# tastatur.net
KiCad netlist of a schematic drawn in EAGLE
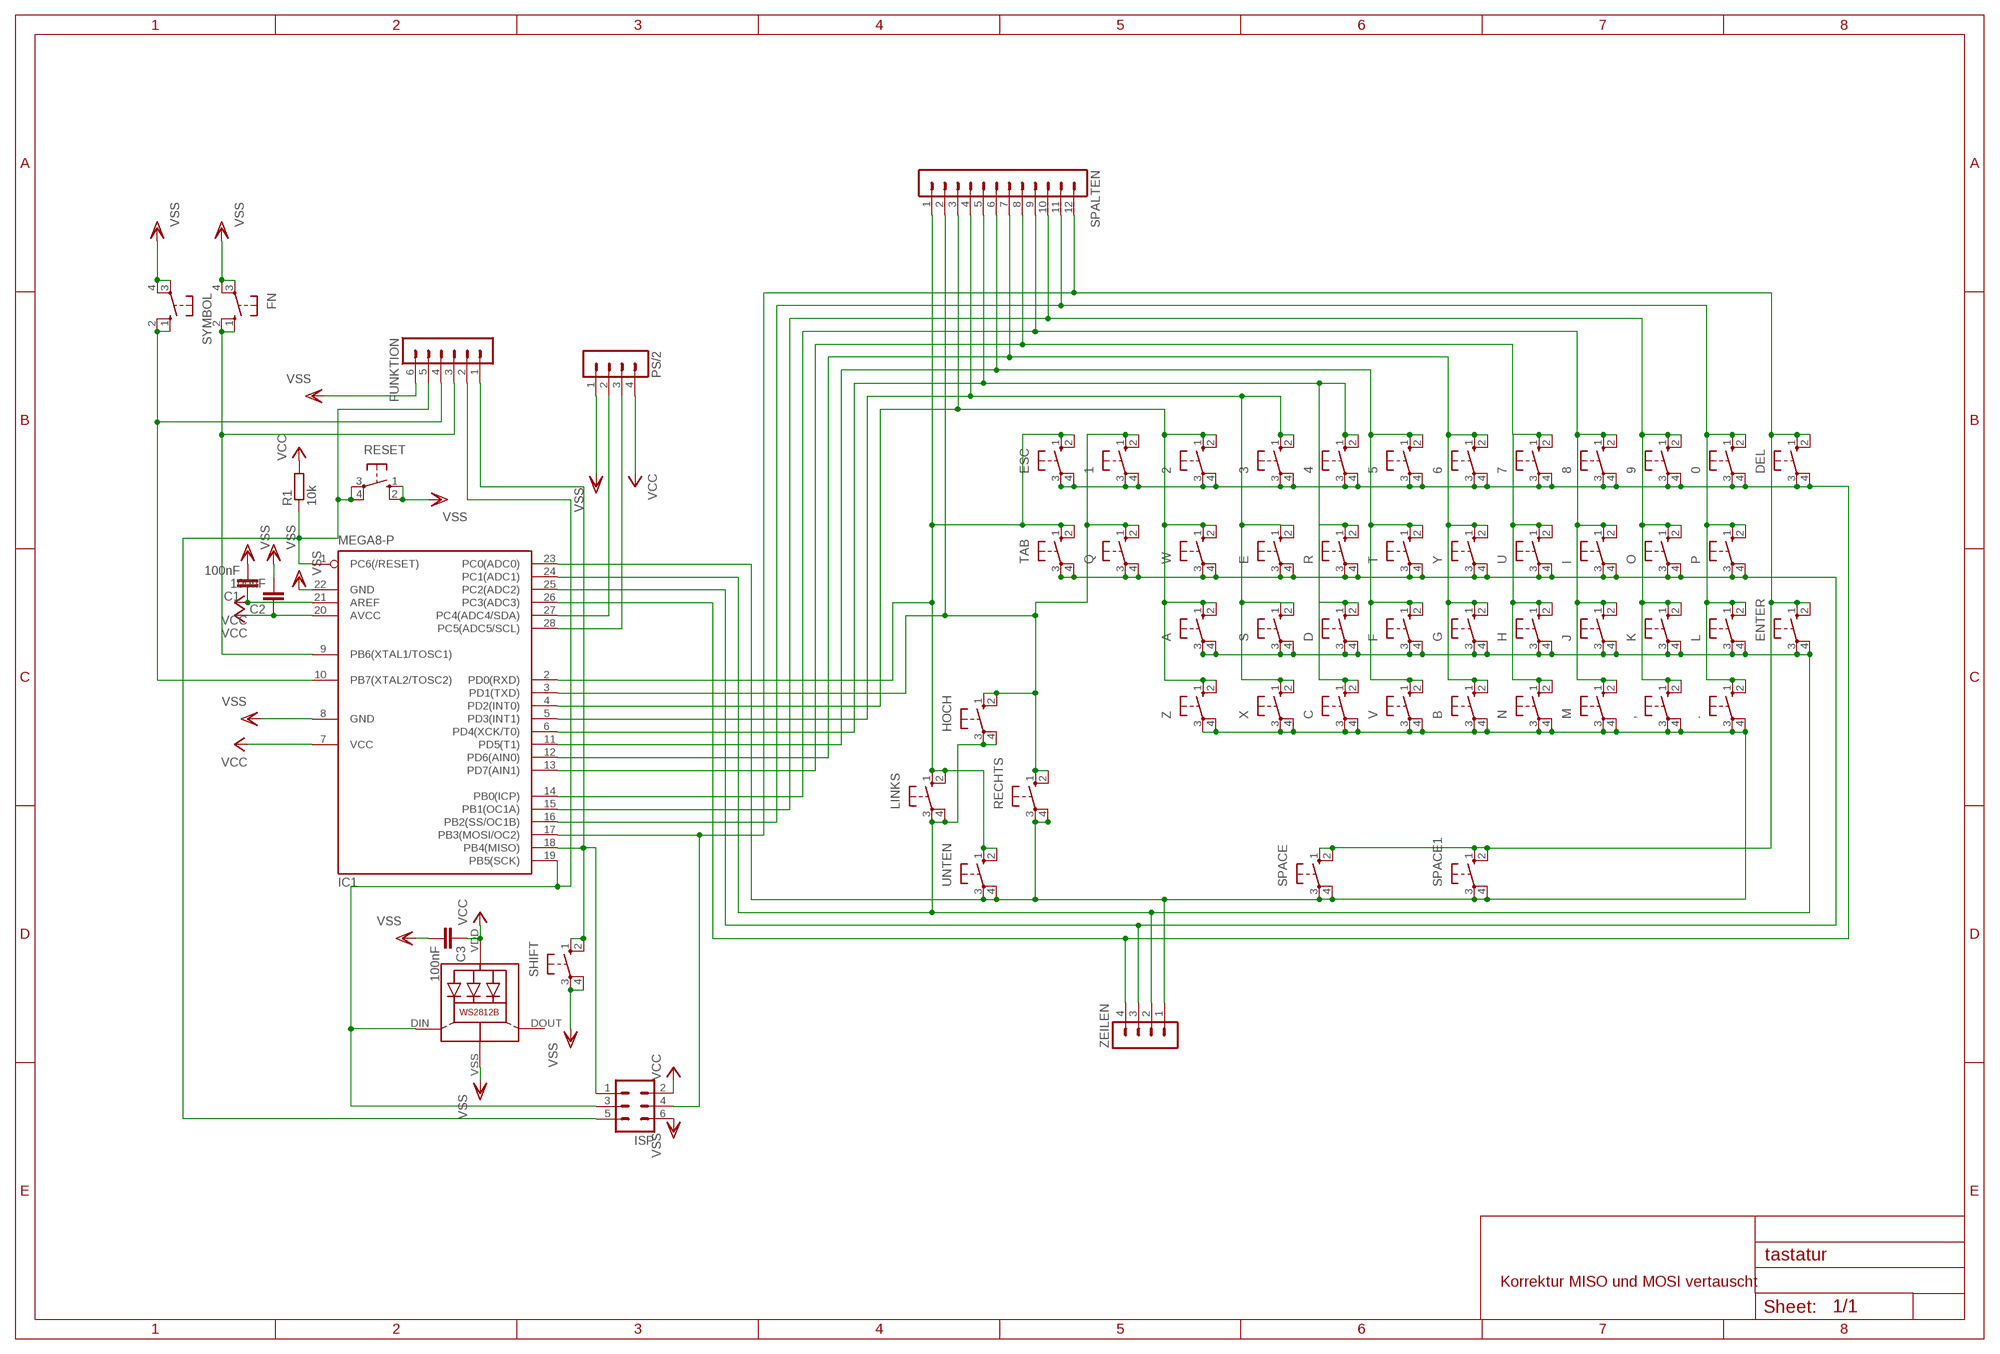
[diagram p0: schematic, sheet 1]

(export (version "E")
  (design (tool "Eeschema 10.0.6"))
  (components
    (comp (ref ",")
      (value "40-XX")
      (footprint "eagle-import:B3F-40XX")
      (fields (field (name "MF") "OMRON COMPONENTS USA") (field (name "MPN") "B3F-4000"))
      (libsource (lib "eagle-import") (part "40-XX"))
    )
    (comp (ref ".")
      (value "40-XX")
      (footprint "eagle-import:B3F-40XX")
      (fields (field (name "MF") "OMRON COMPONENTS USA") (field (name "MPN") "B3F-4000"))
      (libsource (lib "eagle-import") (part "40-XX"))
    )
    (comp (ref "0")
      (value "40-XX")
      (footprint "eagle-import:B3F-40XX")
      (fields (field (name "MF") "OMRON COMPONENTS USA") (field (name "MPN") "B3F-4000"))
      (libsource (lib "eagle-import") (part "40-XX"))
    )
    (comp (ref "1")
      (value "40-XX")
      (footprint "eagle-import:B3F-40XX")
      (fields (field (name "MF") "OMRON COMPONENTS USA") (field (name "MPN") "B3F-4000"))
      (libsource (lib "eagle-import") (part "40-XX"))
    )
    (comp (ref "2")
      (value "40-XX")
      (footprint "eagle-import:B3F-40XX")
      (fields (field (name "MF") "OMRON COMPONENTS USA") (field (name "MPN") "B3F-4000"))
      (libsource (lib "eagle-import") (part "40-XX"))
    )
    (comp (ref "3")
      (value "40-XX")
      (footprint "eagle-import:B3F-40XX")
      (fields (field (name "MF") "OMRON COMPONENTS USA") (field (name "MPN") "B3F-4000"))
      (libsource (lib "eagle-import") (part "40-XX"))
    )
    (comp (ref "4")
      (value "40-XX")
      (footprint "eagle-import:B3F-40XX")
      (fields (field (name "MF") "OMRON COMPONENTS USA") (field (name "MPN") "B3F-4000"))
      (libsource (lib "eagle-import") (part "40-XX"))
    )
    (comp (ref "5")
      (value "40-XX")
      (footprint "eagle-import:B3F-40XX")
      (fields (field (name "MF") "OMRON COMPONENTS USA") (field (name "MPN") "B3F-4000"))
      (libsource (lib "eagle-import") (part "40-XX"))
    )
    (comp (ref "6")
      (value "40-XX")
      (footprint "eagle-import:B3F-40XX")
      (fields (field (name "MF") "OMRON COMPONENTS USA") (field (name "MPN") "B3F-4000"))
      (libsource (lib "eagle-import") (part "40-XX"))
    )
    (comp (ref "7")
      (value "40-XX")
      (footprint "eagle-import:B3F-40XX")
      (fields (field (name "MF") "OMRON COMPONENTS USA") (field (name "MPN") "B3F-4000"))
      (libsource (lib "eagle-import") (part "40-XX"))
    )
    (comp (ref "8")
      (value "40-XX")
      (footprint "eagle-import:B3F-40XX")
      (fields (field (name "MF") "OMRON COMPONENTS USA") (field (name "MPN") "B3F-4000"))
      (libsource (lib "eagle-import") (part "40-XX"))
    )
    (comp (ref "9")
      (value "40-XX")
      (footprint "eagle-import:B3F-40XX")
      (fields (field (name "MF") "OMRON COMPONENTS USA") (field (name "MPN") "B3F-4000"))
      (libsource (lib "eagle-import") (part "40-XX"))
    )
    (comp (ref "A")
      (value "40-XX")
      (footprint "eagle-import:B3F-40XX")
      (fields (field (name "MF") "OMRON COMPONENTS USA") (field (name "MPN") "B3F-4000"))
      (libsource (lib "eagle-import") (part "40-XX"))
    )
    (comp (ref "B")
      (value "40-XX")
      (footprint "eagle-import:B3F-40XX")
      (fields (field (name "MF") "OMRON COMPONENTS USA") (field (name "MPN") "B3F-4000"))
      (libsource (lib "eagle-import") (part "40-XX"))
    )
    (comp (ref "C")
      (value "40-XX")
      (footprint "eagle-import:B3F-40XX")
      (fields (field (name "MF") "OMRON COMPONENTS USA") (field (name "MPN") "B3F-4000"))
      (libsource (lib "eagle-import") (part "40-XX"))
    )
    (comp (ref "C1")
      (value "100nF")
      (footprint "eagle-import:C025-025X050")
      (libsource (lib "eagle-import") (part "C-EU025-025X050"))
    )
    (comp (ref "C2")
      (value "100nF")
      (footprint "eagle-import:C025-025X050")
      (libsource (lib "eagle-import") (part "C-EU025-025X050"))
    )
    (comp (ref "C3")
      (value "100nF")
      (footprint "eagle-import:C025-025X050")
      (libsource (lib "eagle-import") (part "C-EU025-025X050"))
    )
    (comp (ref "D")
      (value "40-XX")
      (footprint "eagle-import:B3F-40XX")
      (fields (field (name "MF") "OMRON COMPONENTS USA") (field (name "MPN") "B3F-4000"))
      (libsource (lib "eagle-import") (part "40-XX"))
    )
    (comp (ref "DEL")
      (value "40-XX")
      (footprint "eagle-import:B3F-40XX")
      (fields (field (name "MF") "OMRON COMPONENTS USA") (field (name "MPN") "B3F-4000"))
      (libsource (lib "eagle-import") (part "40-XX"))
    )
    (comp (ref "E")
      (value "40-XX")
      (footprint "eagle-import:B3F-40XX")
      (fields (field (name "MF") "OMRON COMPONENTS USA") (field (name "MPN") "B3F-4000"))
      (libsource (lib "eagle-import") (part "40-XX"))
    )
    (comp (ref "ENTER")
      (value "40-XX")
      (footprint "eagle-import:B3F-40XX")
      (fields (field (name "MF") "OMRON COMPONENTS USA") (field (name "MPN") "B3F-4000"))
      (libsource (lib "eagle-import") (part "40-XX"))
    )
    (comp (ref "ESC")
      (value "40-XX")
      (footprint "eagle-import:B3F-40XX")
      (fields (field (name "MF") "OMRON COMPONENTS USA") (field (name "MPN") "B3F-4000"))
      (libsource (lib "eagle-import") (part "40-XX"))
    )
    (comp (ref "F")
      (value "40-XX")
      (footprint "eagle-import:B3F-40XX")
      (fields (field (name "MF") "OMRON COMPONENTS USA") (field (name "MPN") "B3F-4000"))
      (libsource (lib "eagle-import") (part "40-XX"))
    )
    (comp (ref "FN")
      (value "40-XX")
      (footprint "eagle-import:B3F-40XX")
      (fields (field (name "MF") "OMRON COMPONENTS USA") (field (name "MPN") "B3F-4000"))
      (libsource (lib "eagle-import") (part "40-XX"))
    )
    (comp (ref "FUNKTION")
      (value "MA06-1")
      (footprint "eagle-import:MA06-1")
      (libsource (lib "eagle-import") (part "MA06-1"))
    )
    (comp (ref "G")
      (value "40-XX")
      (footprint "eagle-import:B3F-40XX")
      (fields (field (name "MF") "OMRON COMPONENTS USA") (field (name "MPN") "B3F-4000"))
      (libsource (lib "eagle-import") (part "40-XX"))
    )
    (comp (ref "H")
      (value "40-XX")
      (footprint "eagle-import:B3F-40XX")
      (fields (field (name "MF") "OMRON COMPONENTS USA") (field (name "MPN") "B3F-4000"))
      (libsource (lib "eagle-import") (part "40-XX"))
    )
    (comp (ref "HOCH")
      (value "40-XX")
      (footprint "eagle-import:B3F-40XX")
      (fields
        (field (name "MF") "OMRON COMPONENTS USA")
        (field (name "MPN") "B3F-4000")
        (field (name "MF_1") "OMRON COMPONENTS USA")
        (field (name "MPN_1") "B3F-4000")
        (field (name "OC_FARNELL") "176434")
        (field (name "OC_NEWARK") "36K3105")
      )
      (libsource (lib "eagle-import") (part "40-XX"))
    )
    (comp (ref "I")
      (value "40-XX")
      (footprint "eagle-import:B3F-40XX")
      (fields (field (name "MF") "OMRON COMPONENTS USA") (field (name "MPN") "B3F-4000"))
      (libsource (lib "eagle-import") (part "40-XX"))
    )
    (comp (ref "IC1")
      (value "MEGA8-P")
      (footprint "eagle-import:DIL28-3")
      (libsource (lib "eagle-import") (part "MEGA8-P"))
    )
    (comp (ref "ISP")
      (value "ML6L")
      (footprint "eagle-import:ML6L")
      (libsource (lib "eagle-import") (part "ML6L"))
    )
    (comp (ref "J")
      (value "40-XX")
      (footprint "eagle-import:B3F-40XX")
      (fields (field (name "MF") "OMRON COMPONENTS USA") (field (name "MPN") "B3F-4000"))
      (libsource (lib "eagle-import") (part "40-XX"))
    )
    (comp (ref "K")
      (value "40-XX")
      (footprint "eagle-import:B3F-40XX")
      (fields (field (name "MF") "OMRON COMPONENTS USA") (field (name "MPN") "B3F-4000"))
      (libsource (lib "eagle-import") (part "40-XX"))
    )
    (comp (ref "L")
      (value "40-XX")
      (footprint "eagle-import:B3F-40XX")
      (fields (field (name "MF") "OMRON COMPONENTS USA") (field (name "MPN") "B3F-4000"))
      (libsource (lib "eagle-import") (part "40-XX"))
    )
    (comp (ref "LED1")
      (value "WS2812B")
      (footprint "eagle-import:WS2812B")
      (libsource (lib "eagle-import") (part "WS2812B"))
    )
    (comp (ref "LINKS")
      (value "40-XX")
      (footprint "eagle-import:B3F-40XX")
      (fields
        (field (name "MF") "OMRON COMPONENTS USA")
        (field (name "MPN") "B3F-4000")
        (field (name "MF_1") "OMRON COMPONENTS USA")
        (field (name "MPN_1") "B3F-4000")
        (field (name "OC_FARNELL") "176434")
        (field (name "OC_NEWARK") "36K3105")
      )
      (libsource (lib "eagle-import") (part "40-XX"))
    )
    (comp (ref "M")
      (value "40-XX")
      (footprint "eagle-import:B3F-40XX")
      (fields (field (name "MF") "OMRON COMPONENTS USA") (field (name "MPN") "B3F-4000"))
      (libsource (lib "eagle-import") (part "40-XX"))
    )
    (comp (ref "N")
      (value "40-XX")
      (footprint "eagle-import:B3F-40XX")
      (fields (field (name "MF") "OMRON COMPONENTS USA") (field (name "MPN") "B3F-4000"))
      (libsource (lib "eagle-import") (part "40-XX"))
    )
    (comp (ref "O")
      (value "40-XX")
      (footprint "eagle-import:B3F-40XX")
      (fields (field (name "MF") "OMRON COMPONENTS USA") (field (name "MPN") "B3F-4000"))
      (libsource (lib "eagle-import") (part "40-XX"))
    )
    (comp (ref "P")
      (value "40-XX")
      (footprint "eagle-import:B3F-40XX")
      (fields (field (name "MF") "OMRON COMPONENTS USA") (field (name "MPN") "B3F-4000"))
      (libsource (lib "eagle-import") (part "40-XX"))
    )
    (comp (ref "PS/2")
      (value "MA04-1")
      (footprint "eagle-import:MA04-1")
      (libsource (lib "eagle-import") (part "MA04-1"))
    )
    (comp (ref "Q")
      (value "40-XX")
      (footprint "eagle-import:B3F-40XX")
      (fields (field (name "MF") "OMRON COMPONENTS USA") (field (name "MPN") "B3F-4000"))
      (libsource (lib "eagle-import") (part "40-XX"))
    )
    (comp (ref "R")
      (value "40-XX")
      (footprint "eagle-import:B3F-40XX")
      (fields (field (name "MF") "OMRON COMPONENTS USA") (field (name "MPN") "B3F-4000"))
      (libsource (lib "eagle-import") (part "40-XX"))
    )
    (comp (ref "R1")
      (value "10k")
      (footprint "eagle-import:0204_7")
      (libsource (lib "eagle-import") (part "R-EU_0204/7"))
    )
    (comp (ref "RECHTS")
      (value "40-XX")
      (footprint "eagle-import:B3F-40XX")
      (fields
        (field (name "MF") "OMRON COMPONENTS USA")
        (field (name "MPN") "B3F-4000")
        (field (name "MF_1") "OMRON COMPONENTS USA")
        (field (name "MPN_1") "B3F-4000")
        (field (name "OC_FARNELL") "176434")
        (field (name "OC_NEWARK") "36K3105")
      )
      (libsource (lib "eagle-import") (part "40-XX"))
    )
    (comp (ref "RESET")
      (value "10-XX")
      (footprint "eagle-import:B3F-10XX")
      (fields (field (name "MPN") "B3F-1000"))
      (libsource (lib "eagle-import") (part "10-XX"))
    )
    (comp (ref "S")
      (value "40-XX")
      (footprint "eagle-import:B3F-40XX")
      (fields (field (name "MF") "OMRON COMPONENTS USA") (field (name "MPN") "B3F-4000"))
      (libsource (lib "eagle-import") (part "40-XX"))
    )
    (comp (ref "SHIFT")
      (value "40-XX")
      (footprint "eagle-import:B3F-40XX")
      (fields (field (name "MF") "OMRON COMPONENTS USA") (field (name "MPN") "B3F-4000"))
      (libsource (lib "eagle-import") (part "40-XX"))
    )
    (comp (ref "SPACE")
      (value "40-XX")
      (footprint "eagle-import:B3F-40XX")
      (fields
        (field (name "MF") "OMRON COMPONENTS USA")
        (field (name "MPN") "B3F-4000")
        (field (name "MF_1") "OMRON COMPONENTS USA")
        (field (name "MPN_1") "B3F-4000")
        (field (name "OC_FARNELL") "176434")
        (field (name "OC_NEWARK") "36K3105")
      )
      (libsource (lib "eagle-import") (part "40-XX"))
    )
    (comp (ref "SPACE1")
      (value "40-XX")
      (footprint "eagle-import:B3F-40XX")
      (fields (field (name "MF") "OMRON COMPONENTS USA") (field (name "MPN") "B3F-4000"))
      (libsource (lib "eagle-import") (part "40-XX"))
    )
    (comp (ref "SPALTEN")
      (value "MA12-1")
      (footprint "eagle-import:MA12-1")
      (libsource (lib "eagle-import") (part "MA12-1"))
    )
    (comp (ref "SYMBOL")
      (value "40-XX")
      (footprint "eagle-import:B3F-40XX")
      (fields (field (name "MF") "OMRON COMPONENTS USA") (field (name "MPN") "B3F-4000"))
      (libsource (lib "eagle-import") (part "40-XX"))
    )
    (comp (ref "T")
      (value "40-XX")
      (footprint "eagle-import:B3F-40XX")
      (fields (field (name "MF") "OMRON COMPONENTS USA") (field (name "MPN") "B3F-4000"))
      (libsource (lib "eagle-import") (part "40-XX"))
    )
    (comp (ref "TAB")
      (value "40-XX")
      (footprint "eagle-import:B3F-40XX")
      (fields (field (name "MF") "OMRON COMPONENTS USA") (field (name "MPN") "B3F-4000"))
      (libsource (lib "eagle-import") (part "40-XX"))
    )
    (comp (ref "U")
      (value "40-XX")
      (footprint "eagle-import:B3F-40XX")
      (fields (field (name "MF") "OMRON COMPONENTS USA") (field (name "MPN") "B3F-4000"))
      (libsource (lib "eagle-import") (part "40-XX"))
    )
    (comp (ref "UNTEN")
      (value "40-XX")
      (footprint "eagle-import:B3F-40XX")
      (fields
        (field (name "MF") "OMRON COMPONENTS USA")
        (field (name "MPN") "B3F-4000")
        (field (name "MF_1") "OMRON COMPONENTS USA")
        (field (name "MPN_1") "B3F-4000")
        (field (name "OC_FARNELL") "176434")
        (field (name "OC_NEWARK") "36K3105")
      )
      (libsource (lib "eagle-import") (part "40-XX"))
    )
    (comp (ref "V")
      (value "40-XX")
      (footprint "eagle-import:B3F-40XX")
      (fields (field (name "MF") "OMRON COMPONENTS USA") (field (name "MPN") "B3F-4000"))
      (libsource (lib "eagle-import") (part "40-XX"))
    )
    (comp (ref "W")
      (value "40-XX")
      (footprint "eagle-import:B3F-40XX")
      (fields (field (name "MF") "OMRON COMPONENTS USA") (field (name "MPN") "B3F-4000"))
      (libsource (lib "eagle-import") (part "40-XX"))
    )
    (comp (ref "X")
      (value "40-XX")
      (footprint "eagle-import:B3F-40XX")
      (fields (field (name "MF") "OMRON COMPONENTS USA") (field (name "MPN") "B3F-4000"))
      (libsource (lib "eagle-import") (part "40-XX"))
    )
    (comp (ref "Y")
      (value "40-XX")
      (footprint "eagle-import:B3F-40XX")
      (fields (field (name "MF") "OMRON COMPONENTS USA") (field (name "MPN") "B3F-4000"))
      (libsource (lib "eagle-import") (part "40-XX"))
    )
    (comp (ref "Z")
      (value "40-XX")
      (footprint "eagle-import:B3F-40XX")
      (fields (field (name "MF") "OMRON COMPONENTS USA") (field (name "MPN") "B3F-4000"))
      (libsource (lib "eagle-import") (part "40-XX"))
    )
    (comp (ref "ZEILEN")
      (value "MA04-1")
      (footprint "eagle-import:MA04-1")
      (fields (field (name "OC_FARNELL") "unknown") (field (name "OC_NEWARK") "unknown"))
      (libsource (lib "eagle-import") (part "MA04-1"))
    )
  )
  (nets
    (net (code "1") (name "Net-(,-P)") (class "Default")
      (node (ref ",") (pin "3") (pinfunction "P_3") (pintype "passive"))
      (node (ref ",") (pin "4") (pinfunction "P1_4") (pintype "passive"))
      (node (ref ".") (pin "3") (pinfunction "P_3") (pintype "passive"))
      (node (ref ".") (pin "4") (pinfunction "P1_4") (pintype "passive"))
      (node (ref "B") (pin "3") (pinfunction "P_3") (pintype "passive"))
      (node (ref "B") (pin "4") (pinfunction "P1_4") (pintype "passive"))
      (node (ref "C") (pin "3") (pinfunction "P_3") (pintype "passive"))
      (node (ref "C") (pin "4") (pinfunction "P1_4") (pintype "passive"))
      (node (ref "IC1") (pin "23") (pinfunction "PC0(ADC0)_23") (pintype "bidirectional"))
      (node (ref "M") (pin "3") (pinfunction "P_3") (pintype "passive"))
      (node (ref "M") (pin "4") (pinfunction "P1_4") (pintype "passive"))
      (node (ref "N") (pin "3") (pinfunction "P_3") (pintype "passive"))
      (node (ref "N") (pin "4") (pinfunction "P1_4") (pintype "passive"))
      (node (ref "RECHTS") (pin "3") (pinfunction "P_3") (pintype "passive"))
      (node (ref "RECHTS") (pin "4") (pinfunction "P1_4") (pintype "passive"))
      (node (ref "SPACE") (pin "3") (pinfunction "P_3") (pintype "passive"))
      (node (ref "SPACE") (pin "4") (pinfunction "P1_4") (pintype "passive"))
      (node (ref "SPACE1") (pin "3") (pinfunction "P_3") (pintype "passive"))
      (node (ref "SPACE1") (pin "4") (pinfunction "P1_4") (pintype "passive"))
      (node (ref "UNTEN") (pin "3") (pinfunction "P_3") (pintype "passive"))
      (node (ref "UNTEN") (pin "4") (pinfunction "P1_4") (pintype "passive"))
      (node (ref "V") (pin "3") (pinfunction "P_3") (pintype "passive"))
      (node (ref "V") (pin "4") (pinfunction "P1_4") (pintype "passive"))
      (node (ref "X") (pin "3") (pinfunction "P_3") (pintype "passive"))
      (node (ref "X") (pin "4") (pinfunction "P1_4") (pintype "passive"))
      (node (ref "Z") (pin "3") (pinfunction "P_3") (pintype "passive"))
      (node (ref "Z") (pin "4") (pinfunction "P1_4") (pintype "passive"))
      (node (ref "ZEILEN") (pin "1") (pinfunction "1_1") (pintype "passive"))
    )
    (net (code "2") (name "Net-(,-S)") (class "Default")
      (node (ref ",") (pin "1") (pinfunction "S_1") (pintype "passive"))
      (node (ref ",") (pin "2") (pinfunction "S1_2") (pintype "passive"))
      (node (ref "9") (pin "1") (pinfunction "S_1") (pintype "passive"))
      (node (ref "9") (pin "2") (pinfunction "S1_2") (pintype "passive"))
      (node (ref "IC1") (pin "15") (pinfunction "PB1(OC1A)_15") (pintype "bidirectional"))
      (node (ref "K") (pin "1") (pinfunction "S_1") (pintype "passive"))
      (node (ref "K") (pin "2") (pinfunction "S1_2") (pintype "passive"))
      (node (ref "O") (pin "1") (pinfunction "S_1") (pintype "passive"))
      (node (ref "O") (pin "2") (pinfunction "S1_2") (pintype "passive"))
      (node (ref "SPALTEN") (pin "10") (pinfunction "10_10") (pintype "passive"))
    )
    (net (code "3") (name "Net-(.-S)") (class "Default")
      (node (ref ".") (pin "1") (pinfunction "S_1") (pintype "passive"))
      (node (ref ".") (pin "2") (pinfunction "S1_2") (pintype "passive"))
      (node (ref "0") (pin "1") (pinfunction "S_1") (pintype "passive"))
      (node (ref "0") (pin "2") (pinfunction "S1_2") (pintype "passive"))
      (node (ref "IC1") (pin "16") (pinfunction "PB2(SS/OC1B)_16") (pintype "bidirectional"))
      (node (ref "L") (pin "1") (pinfunction "S_1") (pintype "passive"))
      (node (ref "L") (pin "2") (pinfunction "S1_2") (pintype "passive"))
      (node (ref "P") (pin "1") (pinfunction "S_1") (pintype "passive"))
      (node (ref "P") (pin "2") (pinfunction "S1_2") (pintype "passive"))
      (node (ref "SPALTEN") (pin "11") (pinfunction "11_11") (pintype "passive"))
    )
    (net (code "4") (name "Net-(0-P)") (class "Default")
      (node (ref "0") (pin "3") (pinfunction "P_3") (pintype "passive"))
      (node (ref "0") (pin "4") (pinfunction "P1_4") (pintype "passive"))
      (node (ref "1") (pin "3") (pinfunction "P_3") (pintype "passive"))
      (node (ref "1") (pin "4") (pinfunction "P1_4") (pintype "passive"))
      (node (ref "2") (pin "3") (pinfunction "P_3") (pintype "passive"))
      (node (ref "2") (pin "4") (pinfunction "P1_4") (pintype "passive"))
      (node (ref "3") (pin "3") (pinfunction "P_3") (pintype "passive"))
      (node (ref "3") (pin "4") (pinfunction "P1_4") (pintype "passive"))
      (node (ref "4") (pin "3") (pinfunction "P_3") (pintype "passive"))
      (node (ref "4") (pin "4") (pinfunction "P1_4") (pintype "passive"))
      (node (ref "5") (pin "3") (pinfunction "P_3") (pintype "passive"))
      (node (ref "5") (pin "4") (pinfunction "P1_4") (pintype "passive"))
      (node (ref "6") (pin "3") (pinfunction "P_3") (pintype "passive"))
      (node (ref "6") (pin "4") (pinfunction "P1_4") (pintype "passive"))
      (node (ref "7") (pin "3") (pinfunction "P_3") (pintype "passive"))
      (node (ref "7") (pin "4") (pinfunction "P1_4") (pintype "passive"))
      (node (ref "8") (pin "3") (pinfunction "P_3") (pintype "passive"))
      (node (ref "8") (pin "4") (pinfunction "P1_4") (pintype "passive"))
      (node (ref "9") (pin "3") (pinfunction "P_3") (pintype "passive"))
      (node (ref "9") (pin "4") (pinfunction "P1_4") (pintype "passive"))
      (node (ref "DEL") (pin "3") (pinfunction "P_3") (pintype "passive"))
      (node (ref "DEL") (pin "4") (pinfunction "P1_4") (pintype "passive"))
      (node (ref "ESC") (pin "3") (pinfunction "P_3") (pintype "passive"))
      (node (ref "ESC") (pin "4") (pinfunction "P1_4") (pintype "passive"))
      (node (ref "IC1") (pin "26") (pinfunction "PC3(ADC3)_26") (pintype "bidirectional"))
      (node (ref "ZEILEN") (pin "4") (pinfunction "4_4") (pintype "passive"))
    )
    (net (code "5") (name "Net-(1-S)") (class "Default")
      (node (ref "1") (pin "1") (pinfunction "S_1") (pintype "passive"))
      (node (ref "1") (pin "2") (pinfunction "S1_2") (pintype "passive"))
      (node (ref "HOCH") (pin "1") (pinfunction "S_1") (pintype "passive"))
      (node (ref "HOCH") (pin "2") (pinfunction "S1_2") (pintype "passive"))
      (node (ref "IC1") (pin "3") (pinfunction "PD1(TXD)_3") (pintype "bidirectional"))
      (node (ref "Q") (pin "1") (pinfunction "S_1") (pintype "passive"))
      (node (ref "Q") (pin "2") (pinfunction "S1_2") (pintype "passive"))
      (node (ref "RECHTS") (pin "1") (pinfunction "S_1") (pintype "passive"))
      (node (ref "RECHTS") (pin "2") (pinfunction "S1_2") (pintype "passive"))
      (node (ref "SPALTEN") (pin "2") (pinfunction "2_2") (pintype "passive"))
    )
    (net (code "6") (name "Net-(2-S)") (class "Default")
      (node (ref "2") (pin "1") (pinfunction "S_1") (pintype "passive"))
      (node (ref "2") (pin "2") (pinfunction "S1_2") (pintype "passive"))
      (node (ref "A") (pin "1") (pinfunction "S_1") (pintype "passive"))
      (node (ref "A") (pin "2") (pinfunction "S1_2") (pintype "passive"))
      (node (ref "IC1") (pin "4") (pinfunction "PD2(INT0)_4") (pintype "bidirectional"))
      (node (ref "SPALTEN") (pin "3") (pinfunction "3_3") (pintype "passive"))
      (node (ref "W") (pin "1") (pinfunction "S_1") (pintype "passive"))
      (node (ref "W") (pin "2") (pinfunction "S1_2") (pintype "passive"))
      (node (ref "Z") (pin "1") (pinfunction "S_1") (pintype "passive"))
      (node (ref "Z") (pin "2") (pinfunction "S1_2") (pintype "passive"))
    )
    (net (code "7") (name "Net-(3-S)") (class "Default")
      (node (ref "3") (pin "1") (pinfunction "S_1") (pintype "passive"))
      (node (ref "3") (pin "2") (pinfunction "S1_2") (pintype "passive"))
      (node (ref "E") (pin "1") (pinfunction "S_1") (pintype "passive"))
      (node (ref "E") (pin "2") (pinfunction "S1_2") (pintype "passive"))
      (node (ref "IC1") (pin "5") (pinfunction "PD3(INT1)_5") (pintype "bidirectional"))
      (node (ref "S") (pin "1") (pinfunction "S_1") (pintype "passive"))
      (node (ref "S") (pin "2") (pinfunction "S1_2") (pintype "passive"))
      (node (ref "SPALTEN") (pin "4") (pinfunction "4_4") (pintype "passive"))
      (node (ref "X") (pin "1") (pinfunction "S_1") (pintype "passive"))
      (node (ref "X") (pin "2") (pinfunction "S1_2") (pintype "passive"))
    )
    (net (code "8") (name "Net-(4-S)") (class "Default")
      (node (ref "4") (pin "1") (pinfunction "S_1") (pintype "passive"))
      (node (ref "4") (pin "2") (pinfunction "S1_2") (pintype "passive"))
      (node (ref "C") (pin "1") (pinfunction "S_1") (pintype "passive"))
      (node (ref "C") (pin "2") (pinfunction "S1_2") (pintype "passive"))
      (node (ref "D") (pin "1") (pinfunction "S_1") (pintype "passive"))
      (node (ref "D") (pin "2") (pinfunction "S1_2") (pintype "passive"))
      (node (ref "IC1") (pin "6") (pinfunction "PD4(XCK/T0)_6") (pintype "bidirectional"))
      (node (ref "R") (pin "1") (pinfunction "S_1") (pintype "passive"))
      (node (ref "R") (pin "2") (pinfunction "S1_2") (pintype "passive"))
      (node (ref "SPALTEN") (pin "5") (pinfunction "5_5") (pintype "passive"))
    )
    (net (code "9") (name "Net-(5-S)") (class "Default")
      (node (ref "5") (pin "1") (pinfunction "S_1") (pintype "passive"))
      (node (ref "5") (pin "2") (pinfunction "S1_2") (pintype "passive"))
      (node (ref "F") (pin "1") (pinfunction "S_1") (pintype "passive"))
      (node (ref "F") (pin "2") (pinfunction "S1_2") (pintype "passive"))
      (node (ref "IC1") (pin "11") (pinfunction "PD5(T1)_11") (pintype "bidirectional"))
      (node (ref "SPALTEN") (pin "6") (pinfunction "6_6") (pintype "passive"))
      (node (ref "T") (pin "1") (pinfunction "S_1") (pintype "passive"))
      (node (ref "T") (pin "2") (pinfunction "S1_2") (pintype "passive"))
      (node (ref "V") (pin "1") (pinfunction "S_1") (pintype "passive"))
      (node (ref "V") (pin "2") (pinfunction "S1_2") (pintype "passive"))
    )
    (net (code "10") (name "Net-(6-S)") (class "Default")
      (node (ref "6") (pin "1") (pinfunction "S_1") (pintype "passive"))
      (node (ref "6") (pin "2") (pinfunction "S1_2") (pintype "passive"))
      (node (ref "B") (pin "1") (pinfunction "S_1") (pintype "passive"))
      (node (ref "B") (pin "2") (pinfunction "S1_2") (pintype "passive"))
      (node (ref "G") (pin "1") (pinfunction "S_1") (pintype "passive"))
      (node (ref "G") (pin "2") (pinfunction "S1_2") (pintype "passive"))
      (node (ref "IC1") (pin "12") (pinfunction "PD6(AIN0)_12") (pintype "bidirectional"))
      (node (ref "SPALTEN") (pin "7") (pinfunction "7_7") (pintype "passive"))
      (node (ref "Y") (pin "1") (pinfunction "S_1") (pintype "passive"))
      (node (ref "Y") (pin "2") (pinfunction "S1_2") (pintype "passive"))
    )
    (net (code "11") (name "Net-(7-S)") (class "Default")
      (node (ref "7") (pin "1") (pinfunction "S_1") (pintype "passive"))
      (node (ref "7") (pin "2") (pinfunction "S1_2") (pintype "passive"))
      (node (ref "H") (pin "1") (pinfunction "S_1") (pintype "passive"))
      (node (ref "H") (pin "2") (pinfunction "S1_2") (pintype "passive"))
      (node (ref "IC1") (pin "13") (pinfunction "PD7(AIN1)_13") (pintype "bidirectional"))
      (node (ref "N") (pin "1") (pinfunction "S_1") (pintype "passive"))
      (node (ref "N") (pin "2") (pinfunction "S1_2") (pintype "passive"))
      (node (ref "SPALTEN") (pin "8") (pinfunction "8_8") (pintype "passive"))
      (node (ref "U") (pin "1") (pinfunction "S_1") (pintype "passive"))
      (node (ref "U") (pin "2") (pinfunction "S1_2") (pintype "passive"))
    )
    (net (code "12") (name "Net-(8-S)") (class "Default")
      (node (ref "8") (pin "1") (pinfunction "S_1") (pintype "passive"))
      (node (ref "8") (pin "2") (pinfunction "S1_2") (pintype "passive"))
      (node (ref "I") (pin "1") (pinfunction "S_1") (pintype "passive"))
      (node (ref "I") (pin "2") (pinfunction "S1_2") (pintype "passive"))
      (node (ref "IC1") (pin "14") (pinfunction "PB0(ICP)_14") (pintype "bidirectional"))
      (node (ref "J") (pin "1") (pinfunction "S_1") (pintype "passive"))
      (node (ref "J") (pin "2") (pinfunction "S1_2") (pintype "passive"))
      (node (ref "M") (pin "1") (pinfunction "S_1") (pintype "passive"))
      (node (ref "M") (pin "2") (pinfunction "S1_2") (pintype "passive"))
      (node (ref "SPALTEN") (pin "9") (pinfunction "9_9") (pintype "passive"))
    )
    (net (code "13") (name "Net-(A-P)") (class "Default")
      (node (ref "A") (pin "3") (pinfunction "P_3") (pintype "passive"))
      (node (ref "A") (pin "4") (pinfunction "P1_4") (pintype "passive"))
      (node (ref "D") (pin "3") (pinfunction "P_3") (pintype "passive"))
      (node (ref "D") (pin "4") (pinfunction "P1_4") (pintype "passive"))
      (node (ref "ENTER") (pin "3") (pinfunction "P_3") (pintype "passive"))
      (node (ref "ENTER") (pin "4") (pinfunction "P1_4") (pintype "passive"))
      (node (ref "F") (pin "3") (pinfunction "P_3") (pintype "passive"))
      (node (ref "F") (pin "4") (pinfunction "P1_4") (pintype "passive"))
      (node (ref "G") (pin "3") (pinfunction "P_3") (pintype "passive"))
      (node (ref "G") (pin "4") (pinfunction "P1_4") (pintype "passive"))
      (node (ref "H") (pin "3") (pinfunction "P_3") (pintype "passive"))
      (node (ref "H") (pin "4") (pinfunction "P1_4") (pintype "passive"))
      (node (ref "HOCH") (pin "3") (pinfunction "P_3") (pintype "passive"))
      (node (ref "HOCH") (pin "4") (pinfunction "P1_4") (pintype "passive"))
      (node (ref "IC1") (pin "24") (pinfunction "PC1(ADC1)_24") (pintype "bidirectional"))
      (node (ref "J") (pin "3") (pinfunction "P_3") (pintype "passive"))
      (node (ref "J") (pin "4") (pinfunction "P1_4") (pintype "passive"))
      (node (ref "K") (pin "3") (pinfunction "P_3") (pintype "passive"))
      (node (ref "K") (pin "4") (pinfunction "P1_4") (pintype "passive"))
      (node (ref "L") (pin "3") (pinfunction "P_3") (pintype "passive"))
      (node (ref "L") (pin "4") (pinfunction "P1_4") (pintype "passive"))
      (node (ref "LINKS") (pin "3") (pinfunction "P_3") (pintype "passive"))
      (node (ref "LINKS") (pin "4") (pinfunction "P1_4") (pintype "passive"))
      (node (ref "S") (pin "3") (pinfunction "P_3") (pintype "passive"))
      (node (ref "S") (pin "4") (pinfunction "P1_4") (pintype "passive"))
      (node (ref "ZEILEN") (pin "2") (pinfunction "2_2") (pintype "passive"))
    )
    (net (code "14") (name "Net-(DEL-S)") (class "Default")
      (node (ref "DEL") (pin "1") (pinfunction "S_1") (pintype "passive"))
      (node (ref "DEL") (pin "2") (pinfunction "S1_2") (pintype "passive"))
      (node (ref "ENTER") (pin "1") (pinfunction "S_1") (pintype "passive"))
      (node (ref "ENTER") (pin "2") (pinfunction "S1_2") (pintype "passive"))
      (node (ref "IC1") (pin "17") (pinfunction "PB3(MOSI/OC2)_17") (pintype "bidirectional"))
      (node (ref "ISP") (pin "4") (pinfunction "4_4") (pintype "passive"))
      (node (ref "SPACE") (pin "1") (pinfunction "S_1") (pintype "passive"))
      (node (ref "SPACE") (pin "2") (pinfunction "S1_2") (pintype "passive"))
      (node (ref "SPACE1") (pin "1") (pinfunction "S_1") (pintype "passive"))
      (node (ref "SPACE1") (pin "2") (pinfunction "S1_2") (pintype "passive"))
      (node (ref "SPALTEN") (pin "12") (pinfunction "12_12") (pintype "passive"))
    )
    (net (code "15") (name "Net-(E-P)") (class "Default")
      (node (ref "E") (pin "3") (pinfunction "P_3") (pintype "passive"))
      (node (ref "E") (pin "4") (pinfunction "P1_4") (pintype "passive"))
      (node (ref "I") (pin "3") (pinfunction "P_3") (pintype "passive"))
      (node (ref "I") (pin "4") (pinfunction "P1_4") (pintype "passive"))
      (node (ref "IC1") (pin "25") (pinfunction "PC2(ADC2)_25") (pintype "bidirectional"))
      (node (ref "O") (pin "3") (pinfunction "P_3") (pintype "passive"))
      (node (ref "O") (pin "4") (pinfunction "P1_4") (pintype "passive"))
      (node (ref "P") (pin "3") (pinfunction "P_3") (pintype "passive"))
      (node (ref "P") (pin "4") (pinfunction "P1_4") (pintype "passive"))
      (node (ref "Q") (pin "3") (pinfunction "P_3") (pintype "passive"))
      (node (ref "Q") (pin "4") (pinfunction "P1_4") (pintype "passive"))
      (node (ref "R") (pin "3") (pinfunction "P_3") (pintype "passive"))
      (node (ref "R") (pin "4") (pinfunction "P1_4") (pintype "passive"))
      (node (ref "T") (pin "3") (pinfunction "P_3") (pintype "passive"))
      (node (ref "T") (pin "4") (pinfunction "P1_4") (pintype "passive"))
      (node (ref "TAB") (pin "3") (pinfunction "P_3") (pintype "passive"))
      (node (ref "TAB") (pin "4") (pinfunction "P1_4") (pintype "passive"))
      (node (ref "U") (pin "3") (pinfunction "P_3") (pintype "passive"))
      (node (ref "U") (pin "4") (pinfunction "P1_4") (pintype "passive"))
      (node (ref "W") (pin "3") (pinfunction "P_3") (pintype "passive"))
      (node (ref "W") (pin "4") (pinfunction "P1_4") (pintype "passive"))
      (node (ref "Y") (pin "3") (pinfunction "P_3") (pintype "passive"))
      (node (ref "Y") (pin "4") (pinfunction "P1_4") (pintype "passive"))
      (node (ref "ZEILEN") (pin "3") (pinfunction "3_3") (pintype "passive"))
    )
    (net (code "16") (name "Net-(ESC-S)") (class "Default")
      (node (ref "ESC") (pin "1") (pinfunction "S_1") (pintype "passive"))
      (node (ref "ESC") (pin "2") (pinfunction "S1_2") (pintype "passive"))
      (node (ref "IC1") (pin "2") (pinfunction "PD0(RXD)_2") (pintype "bidirectional"))
      (node (ref "LINKS") (pin "1") (pinfunction "S_1") (pintype "passive"))
      (node (ref "LINKS") (pin "2") (pinfunction "S1_2") (pintype "passive"))
      (node (ref "SPALTEN") (pin "1") (pinfunction "1_1") (pintype "passive"))
      (node (ref "TAB") (pin "1") (pinfunction "S_1") (pintype "passive"))
      (node (ref "TAB") (pin "2") (pinfunction "S1_2") (pintype "passive"))
      (node (ref "UNTEN") (pin "1") (pinfunction "S_1") (pintype "passive"))
      (node (ref "UNTEN") (pin "2") (pinfunction "S1_2") (pintype "passive"))
    )
    (net (code "17") (name "Net-(FN-S)") (class "Default")
      (node (ref "FN") (pin "1") (pinfunction "S_1") (pintype "passive"))
      (node (ref "FN") (pin "2") (pinfunction "S1_2") (pintype "passive"))
      (node (ref "FUNKTION") (pin "3") (pinfunction "3_3") (pintype "passive"))
      (node (ref "IC1") (pin "9") (pinfunction "PB6(XTAL1/TOSC1)_9") (pintype "bidirectional"))
    )
    (net (code "18") (name "Net-(IC1-PB4(MISO))") (class "Default")
      (node (ref "FUNKTION") (pin "1") (pinfunction "1_1") (pintype "passive"))
      (node (ref "IC1") (pin "18") (pinfunction "PB4(MISO)_18") (pintype "bidirectional"))
      (node (ref "ISP") (pin "1") (pinfunction "1_1") (pintype "passive"))
      (node (ref "SHIFT") (pin "1") (pinfunction "S_1") (pintype "passive"))
      (node (ref "SHIFT") (pin "2") (pinfunction "S1_2") (pintype "passive"))
    )
    (net (code "19") (name "Net-(IC1-PB5(SCK))") (class "Default")
      (node (ref "FUNKTION") (pin "2") (pinfunction "2_2") (pintype "passive"))
      (node (ref "IC1") (pin "19") (pinfunction "PB5(SCK)_19") (pintype "bidirectional"))
      (node (ref "ISP") (pin "3") (pinfunction "3_3") (pintype "passive"))
      (node (ref "LED1") (pin "DIN") (pinfunction "DI_DIN") (pintype "input"))
    )
    (net (code "20") (name "Net-(IC1-PB7(XTAL2{slash}TOSC2))") (class "Default")
      (node (ref "FUNKTION") (pin "4") (pinfunction "4_4") (pintype "passive"))
      (node (ref "IC1") (pin "10") (pinfunction "PB7(XTAL2/TOSC2)_10") (pintype "bidirectional"))
      (node (ref "SYMBOL") (pin "1") (pinfunction "S_1") (pintype "passive"))
      (node (ref "SYMBOL") (pin "2") (pinfunction "S1_2") (pintype "passive"))
    )
    (net (code "21") (name "Net-(IC1-PC4(ADC4{slash}SDA))") (class "Default")
      (node (ref "IC1") (pin "27") (pinfunction "PC4(ADC4/SDA)_27") (pintype "bidirectional"))
      (node (ref "PS/2") (pin "2") (pinfunction "2_2") (pintype "passive"))
    )
    (net (code "22") (name "Net-(IC1-PC5(ADC5{slash}SCL))") (class "Default")
      (node (ref "IC1") (pin "28") (pinfunction "PC5(ADC5/SCL)_28") (pintype "bidirectional"))
      (node (ref "PS/2") (pin "3") (pinfunction "3_3") (pintype "passive"))
    )
    (net (code "23") (name "Net-(IC1-PC6({slash}RESET))") (class "Default")
      (node (ref "FUNKTION") (pin "5") (pinfunction "5_5") (pintype "passive"))
      (node (ref "IC1") (pin "1") (pinfunction "PC6(/RESET)_1") (pintype "bidirectional"))
      (node (ref "ISP") (pin "5") (pinfunction "5_5") (pintype "passive"))
      (node (ref "R1") (pin "1") (pinfunction "1_1") (pintype "passive"))
      (node (ref "RESET") (pin "3") (pinfunction "P_3") (pintype "passive"))
      (node (ref "RESET") (pin "4") (pinfunction "P1_4") (pintype "passive"))
    )
    (net (code "24") (name "VCC") (class "Default")
      (node (ref "C1") (pin "1") (pinfunction "1_1") (pintype "passive"))
      (node (ref "C2") (pin "1") (pinfunction "1_1") (pintype "passive"))
      (node (ref "C3") (pin "1") (pinfunction "1_1") (pintype "passive"))
      (node (ref "IC1") (pin "20") (pinfunction "AVCC_20") (pintype "power_in"))
      (node (ref "IC1") (pin "21") (pinfunction "AREF_21") (pintype "passive"))
      (node (ref "IC1") (pin "7") (pinfunction "VCC_7") (pintype "power_in"))
      (node (ref "ISP") (pin "2") (pinfunction "2_2") (pintype "passive"))
      (node (ref "LED1") (pin "VDD") (pinfunction "VDD_VDD") (pintype "power_in"))
      (node (ref "PS/2") (pin "4") (pinfunction "4_4") (pintype "passive"))
      (node (ref "R1") (pin "2") (pinfunction "2_2") (pintype "passive"))
    )
    (net (code "25") (name "VSS") (class "Default")
      (node (ref "C1") (pin "2") (pinfunction "2_2") (pintype "passive"))
      (node (ref "C2") (pin "2") (pinfunction "2_2") (pintype "passive"))
      (node (ref "C3") (pin "2") (pinfunction "2_2") (pintype "passive"))
      (node (ref "FN") (pin "3") (pinfunction "P_3") (pintype "passive"))
      (node (ref "FN") (pin "4") (pinfunction "P1_4") (pintype "passive"))
      (node (ref "FUNKTION") (pin "6") (pinfunction "6_6") (pintype "passive"))
      (node (ref "IC1") (pin "22") (pinfunction "GND_22") (pintype "power_in"))
      (node (ref "IC1") (pin "8") (pinfunction "GND_8") (pintype "power_in"))
      (node (ref "ISP") (pin "6") (pinfunction "6_6") (pintype "passive"))
      (node (ref "LED1") (pin "VSS") (pinfunction "GND_VSS") (pintype "power_in"))
      (node (ref "PS/2") (pin "1") (pinfunction "1_1") (pintype "passive"))
      (node (ref "RESET") (pin "1") (pinfunction "S_1") (pintype "passive"))
      (node (ref "RESET") (pin "2") (pinfunction "S1_2") (pintype "passive"))
      (node (ref "SHIFT") (pin "3") (pinfunction "P_3") (pintype "passive"))
      (node (ref "SHIFT") (pin "4") (pinfunction "P1_4") (pintype "passive"))
      (node (ref "SYMBOL") (pin "3") (pinfunction "P_3") (pintype "passive"))
      (node (ref "SYMBOL") (pin "4") (pinfunction "P1_4") (pintype "passive"))
    )
    (net (code "26") (name "unconnected-(LED1-DO-PadDOUT)") (class "Default")
      (node (ref "LED1") (pin "DOUT") (pinfunction "DO_DOUT") (pintype "output"))
    )
  )
)
